# voltage_reference.net
KiCad netlist of a schematic drawn in EAGLE
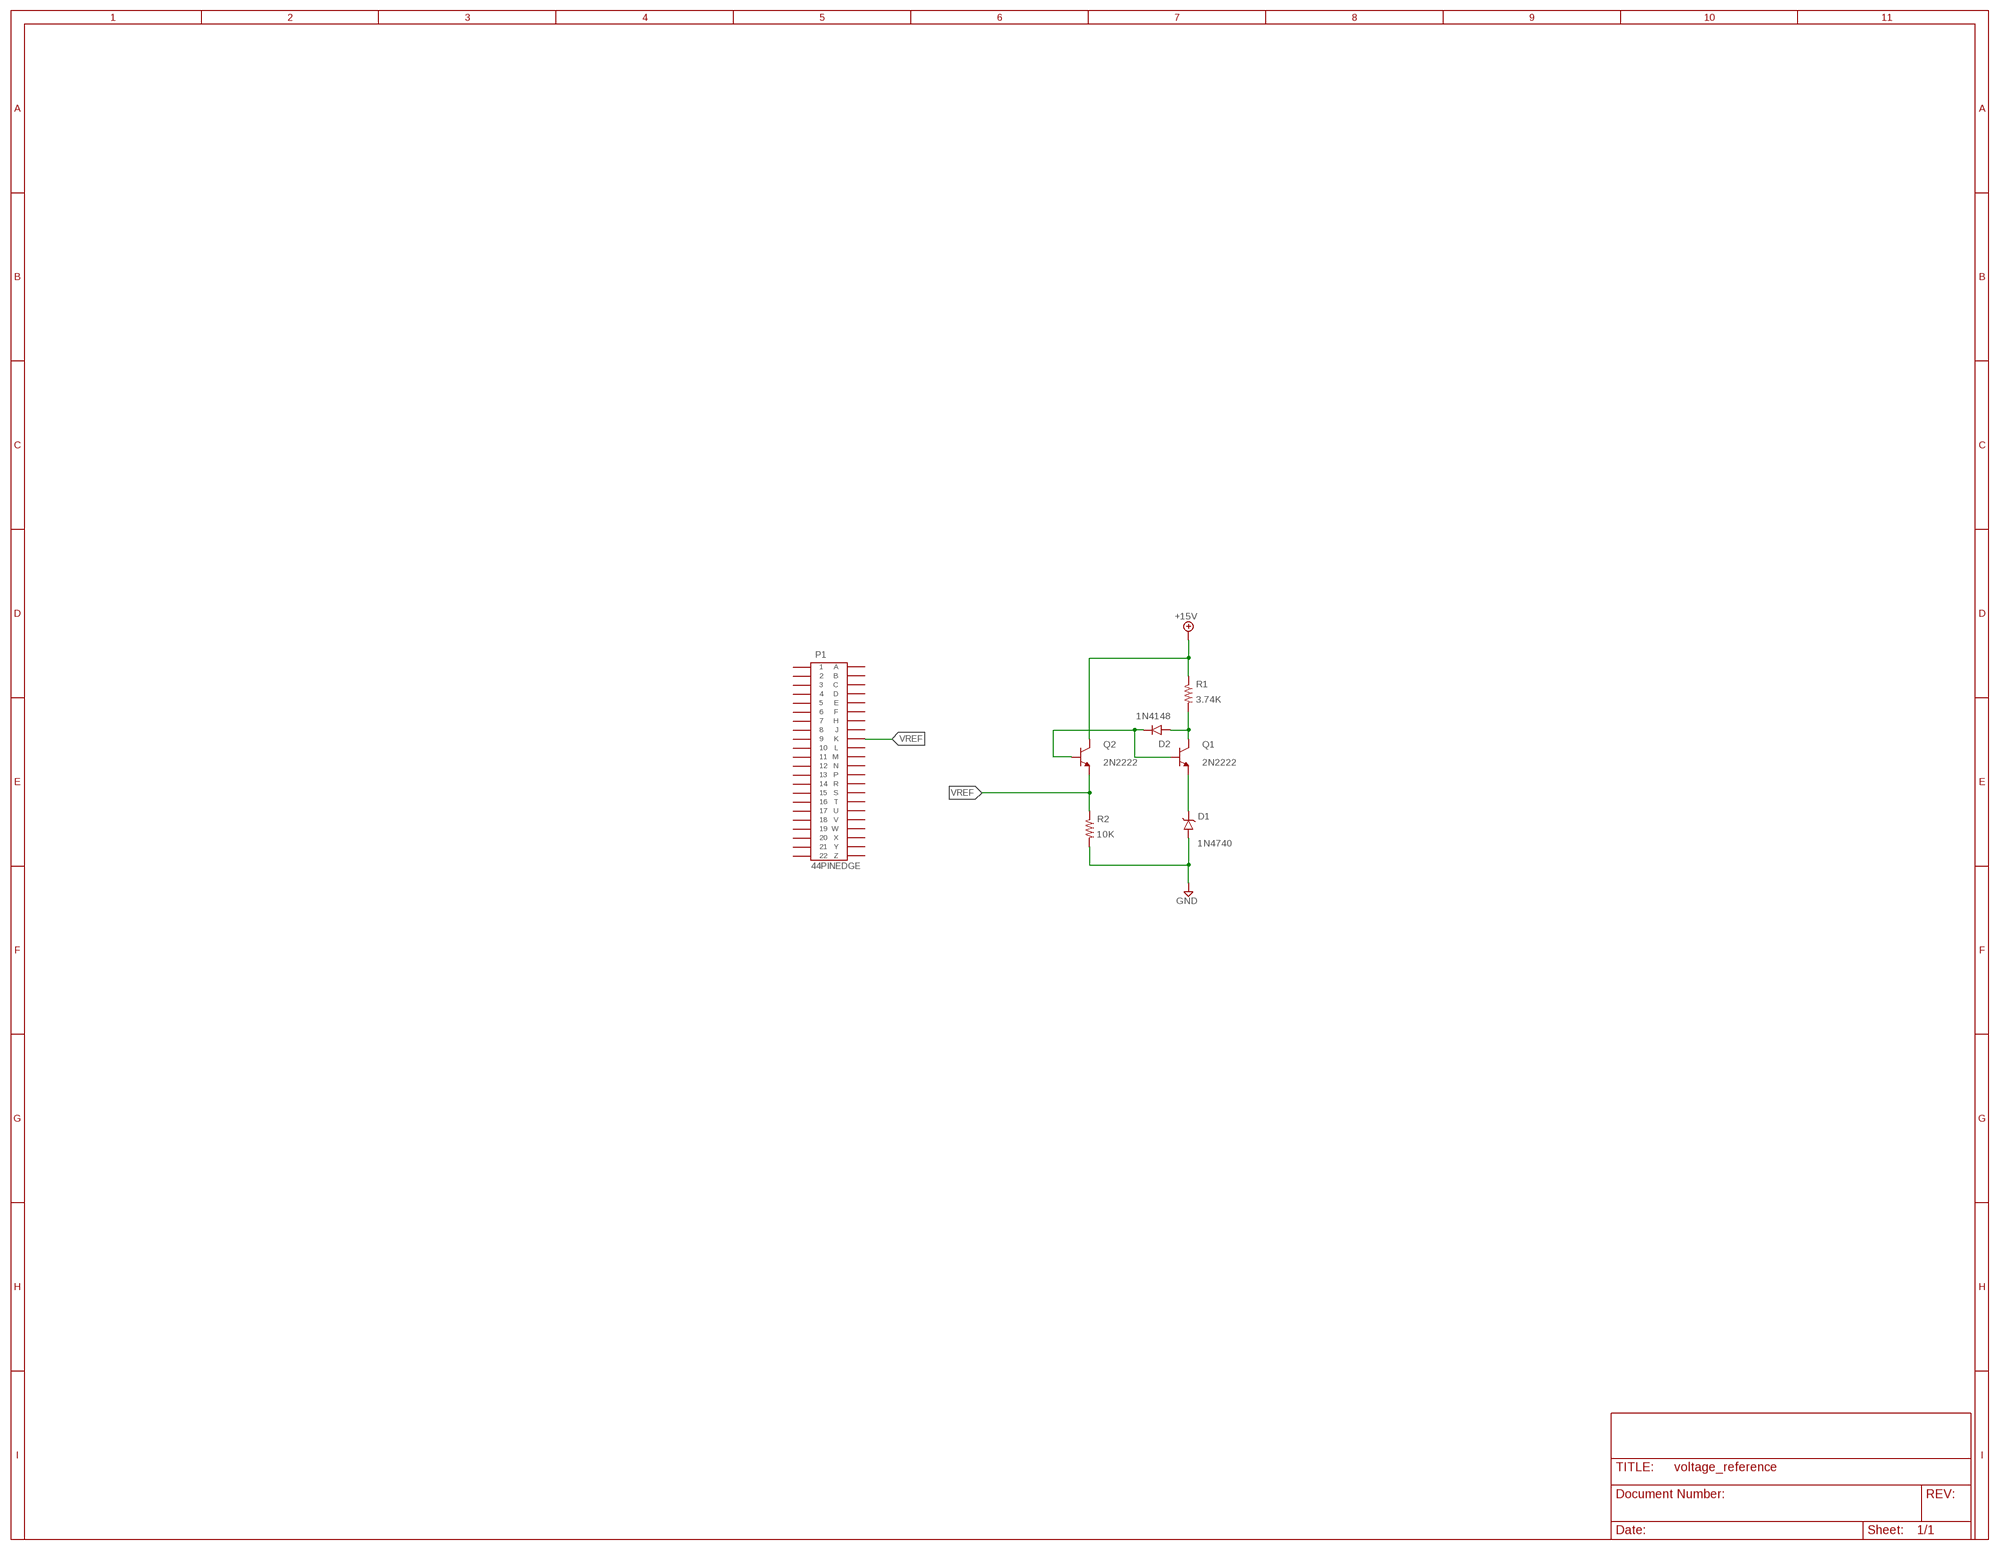
[diagram p0: schematic, sheet 1]

(export (version "E")
  (design (tool "Eeschema 10.0.6"))
  (components
    (comp (ref "D1")
      (value "1N4740")
      (footprint "eagle-import:DO41")
      (libsource (lib "eagle-import") (part "1N4740"))
    )
    (comp (ref "D2")
      (value "1N4148")
      (footprint "eagle-import:DO35-7")
      (libsource (lib "eagle-import") (part "1N4148"))
    )
    (comp (ref "P1")
      (value "44PINEDGE")
      (footprint "eagle-import:44PINEDGE")
      (libsource (lib "eagle-import") (part "44PINEDGE"))
    )
    (comp (ref "Q1")
      (value "2N2222")
      (footprint "eagle-import:TO18")
      (libsource (lib "eagle-import") (part "2N2222"))
    )
    (comp (ref "Q2")
      (value "2N2222")
      (footprint "eagle-import:TO18")
      (libsource (lib "eagle-import") (part "2N2222"))
    )
    (comp (ref "R1")
      (value "3.74K")
      (footprint "eagle-import:0207_10")
      (libsource (lib "eagle-import") (part "R-1/4WATT"))
    )
    (comp (ref "R2")
      (value "10K")
      (footprint "eagle-import:0207_10")
      (libsource (lib "eagle-import") (part "R-1/4WATT"))
    )
  )
  (nets
    (net (code "1") (name "+15V") (class "Default")
      (node (ref "Q2") (pin "3") (pinfunction "C_3") (pintype "passive"))
      (node (ref "R1") (pin "1") (pinfunction "P$1_1") (pintype "passive"))
    )
    (net (code "2") (name "GND") (class "Default")
      (node (ref "D1") (pin "A") (pinfunction "A_A") (pintype "passive"))
      (node (ref "R2") (pin "2") (pinfunction "P$2_2") (pintype "passive"))
    )
    (net (code "3") (name "Net-(Q1-B)") (class "Default")
      (node (ref "D2") (pin "C") (pinfunction "C_C") (pintype "passive"))
      (node (ref "Q1") (pin "2") (pinfunction "B_2") (pintype "passive"))
      (node (ref "Q2") (pin "2") (pinfunction "B_2") (pintype "passive"))
    )
    (net (code "4") (name "Net-(Q1-C)") (class "Default")
      (node (ref "D2") (pin "A") (pinfunction "A_A") (pintype "passive"))
      (node (ref "Q1") (pin "3") (pinfunction "C_3") (pintype "passive"))
      (node (ref "R1") (pin "2") (pinfunction "P$2_2") (pintype "passive"))
    )
    (net (code "5") (name "Net-(Q1-E)") (class "Default")
      (node (ref "D1") (pin "C") (pinfunction "C_C") (pintype "passive"))
      (node (ref "Q1") (pin "1") (pinfunction "E_1") (pintype "passive"))
    )
    (net (code "6") (name "VREF") (class "Default")
      (node (ref "P1") (pin "K") (pinfunction "K_K") (pintype "passive"))
      (node (ref "Q2") (pin "1") (pinfunction "E_1") (pintype "passive"))
      (node (ref "R2") (pin "1") (pinfunction "P$1_1") (pintype "passive"))
    )
    (net (code "7") (name "unconnected-(P1-Pad1)") (class "Default")
      (node (ref "P1") (pin "1") (pinfunction "1_1") (pintype "passive"))
    )
    (net (code "8") (name "unconnected-(P1-Pad2)") (class "Default")
      (node (ref "P1") (pin "2") (pinfunction "2_2") (pintype "passive"))
    )
    (net (code "9") (name "unconnected-(P1-Pad3)") (class "Default")
      (node (ref "P1") (pin "3") (pinfunction "3_3") (pintype "passive"))
    )
    (net (code "10") (name "unconnected-(P1-Pad4)") (class "Default")
      (node (ref "P1") (pin "4") (pinfunction "4_4") (pintype "passive"))
    )
    (net (code "11") (name "unconnected-(P1-Pad5)") (class "Default")
      (node (ref "P1") (pin "5") (pinfunction "5_5") (pintype "passive"))
    )
    (net (code "12") (name "unconnected-(P1-Pad6)") (class "Default")
      (node (ref "P1") (pin "6") (pinfunction "6_6") (pintype "passive"))
    )
    (net (code "13") (name "unconnected-(P1-Pad7)") (class "Default")
      (node (ref "P1") (pin "7") (pinfunction "7_7") (pintype "passive"))
    )
    (net (code "14") (name "unconnected-(P1-Pad8)") (class "Default")
      (node (ref "P1") (pin "8") (pinfunction "8_8") (pintype "passive"))
    )
    (net (code "15") (name "unconnected-(P1-Pad9)") (class "Default")
      (node (ref "P1") (pin "9") (pinfunction "9_9") (pintype "passive"))
    )
    (net (code "16") (name "unconnected-(P1-Pad10)") (class "Default")
      (node (ref "P1") (pin "10") (pinfunction "10_10") (pintype "passive"))
    )
    (net (code "17") (name "unconnected-(P1-Pad11)") (class "Default")
      (node (ref "P1") (pin "11") (pinfunction "11_11") (pintype "passive"))
    )
    (net (code "18") (name "unconnected-(P1-Pad12)") (class "Default")
      (node (ref "P1") (pin "12") (pinfunction "12_12") (pintype "passive"))
    )
    (net (code "19") (name "unconnected-(P1-Pad13)") (class "Default")
      (node (ref "P1") (pin "13") (pinfunction "13_13") (pintype "passive"))
    )
    (net (code "20") (name "unconnected-(P1-Pad14)") (class "Default")
      (node (ref "P1") (pin "14") (pinfunction "14_14") (pintype "passive"))
    )
    (net (code "21") (name "unconnected-(P1-Pad15)") (class "Default")
      (node (ref "P1") (pin "15") (pinfunction "15_15") (pintype "passive"))
    )
    (net (code "22") (name "unconnected-(P1-Pad16)") (class "Default")
      (node (ref "P1") (pin "16") (pinfunction "16_16") (pintype "passive"))
    )
    (net (code "23") (name "unconnected-(P1-Pad17)") (class "Default")
      (node (ref "P1") (pin "17") (pinfunction "17_17") (pintype "passive"))
    )
    (net (code "24") (name "unconnected-(P1-Pad18)") (class "Default")
      (node (ref "P1") (pin "18") (pinfunction "18_18") (pintype "passive"))
    )
    (net (code "25") (name "unconnected-(P1-Pad19)") (class "Default")
      (node (ref "P1") (pin "19") (pinfunction "19_19") (pintype "passive"))
    )
    (net (code "26") (name "unconnected-(P1-Pad20)") (class "Default")
      (node (ref "P1") (pin "20") (pinfunction "20_20") (pintype "passive"))
    )
    (net (code "27") (name "unconnected-(P1-Pad21)") (class "Default")
      (node (ref "P1") (pin "21") (pinfunction "21_21") (pintype "passive"))
    )
    (net (code "28") (name "unconnected-(P1-Pad22)") (class "Default")
      (node (ref "P1") (pin "22") (pinfunction "22_22") (pintype "passive"))
    )
    (net (code "29") (name "unconnected-(P1-PadA)") (class "Default")
      (node (ref "P1") (pin "A") (pinfunction "A_A") (pintype "passive"))
    )
    (net (code "30") (name "unconnected-(P1-PadB)") (class "Default")
      (node (ref "P1") (pin "B") (pinfunction "B_B") (pintype "passive"))
    )
    (net (code "31") (name "unconnected-(P1-PadC)") (class "Default")
      (node (ref "P1") (pin "C") (pinfunction "C_C") (pintype "passive"))
    )
    (net (code "32") (name "unconnected-(P1-PadD)") (class "Default")
      (node (ref "P1") (pin "D") (pinfunction "D_D") (pintype "passive"))
    )
    (net (code "33") (name "unconnected-(P1-PadE)") (class "Default")
      (node (ref "P1") (pin "E") (pinfunction "E_E") (pintype "passive"))
    )
    (net (code "34") (name "unconnected-(P1-PadF)") (class "Default")
      (node (ref "P1") (pin "F") (pinfunction "F_F") (pintype "passive"))
    )
    (net (code "35") (name "unconnected-(P1-PadH)") (class "Default")
      (node (ref "P1") (pin "H") (pinfunction "H_H") (pintype "passive"))
    )
    (net (code "36") (name "unconnected-(P1-PadJ)") (class "Default")
      (node (ref "P1") (pin "J") (pinfunction "J_J") (pintype "passive"))
    )
    (net (code "37") (name "unconnected-(P1-PadL)") (class "Default")
      (node (ref "P1") (pin "L") (pinfunction "L_L") (pintype "passive"))
    )
    (net (code "38") (name "unconnected-(P1-PadM)") (class "Default")
      (node (ref "P1") (pin "M") (pinfunction "M_M") (pintype "passive"))
    )
    (net (code "39") (name "unconnected-(P1-PadN)") (class "Default")
      (node (ref "P1") (pin "N") (pinfunction "N_N") (pintype "passive"))
    )
    (net (code "40") (name "unconnected-(P1-PadP)") (class "Default")
      (node (ref "P1") (pin "P") (pinfunction "P_P") (pintype "passive"))
    )
    (net (code "41") (name "unconnected-(P1-PadR)") (class "Default")
      (node (ref "P1") (pin "R") (pinfunction "R_R") (pintype "passive"))
    )
    (net (code "42") (name "unconnected-(P1-PadS)") (class "Default")
      (node (ref "P1") (pin "S") (pinfunction "S_S") (pintype "passive"))
    )
    (net (code "43") (name "unconnected-(P1-PadT)") (class "Default")
      (node (ref "P1") (pin "T") (pinfunction "T_T") (pintype "passive"))
    )
    (net (code "44") (name "unconnected-(P1-PadU)") (class "Default")
      (node (ref "P1") (pin "U") (pinfunction "U_U") (pintype "passive"))
    )
    (net (code "45") (name "unconnected-(P1-PadV)") (class "Default")
      (node (ref "P1") (pin "V") (pinfunction "V_V") (pintype "passive"))
    )
    (net (code "46") (name "unconnected-(P1-PadW)") (class "Default")
      (node (ref "P1") (pin "W") (pinfunction "W_W") (pintype "passive"))
    )
    (net (code "47") (name "unconnected-(P1-PadX)") (class "Default")
      (node (ref "P1") (pin "X") (pinfunction "X_X") (pintype "passive"))
    )
    (net (code "48") (name "unconnected-(P1-PadY)") (class "Default")
      (node (ref "P1") (pin "Y") (pinfunction "Y_Y") (pintype "passive"))
    )
    (net (code "49") (name "unconnected-(P1-PadZ)") (class "Default")
      (node (ref "P1") (pin "Z") (pinfunction "Z_Z") (pintype "passive"))
    )
  )
)
